# Display.net
KiCad netlist of a schematic drawn in EAGLE
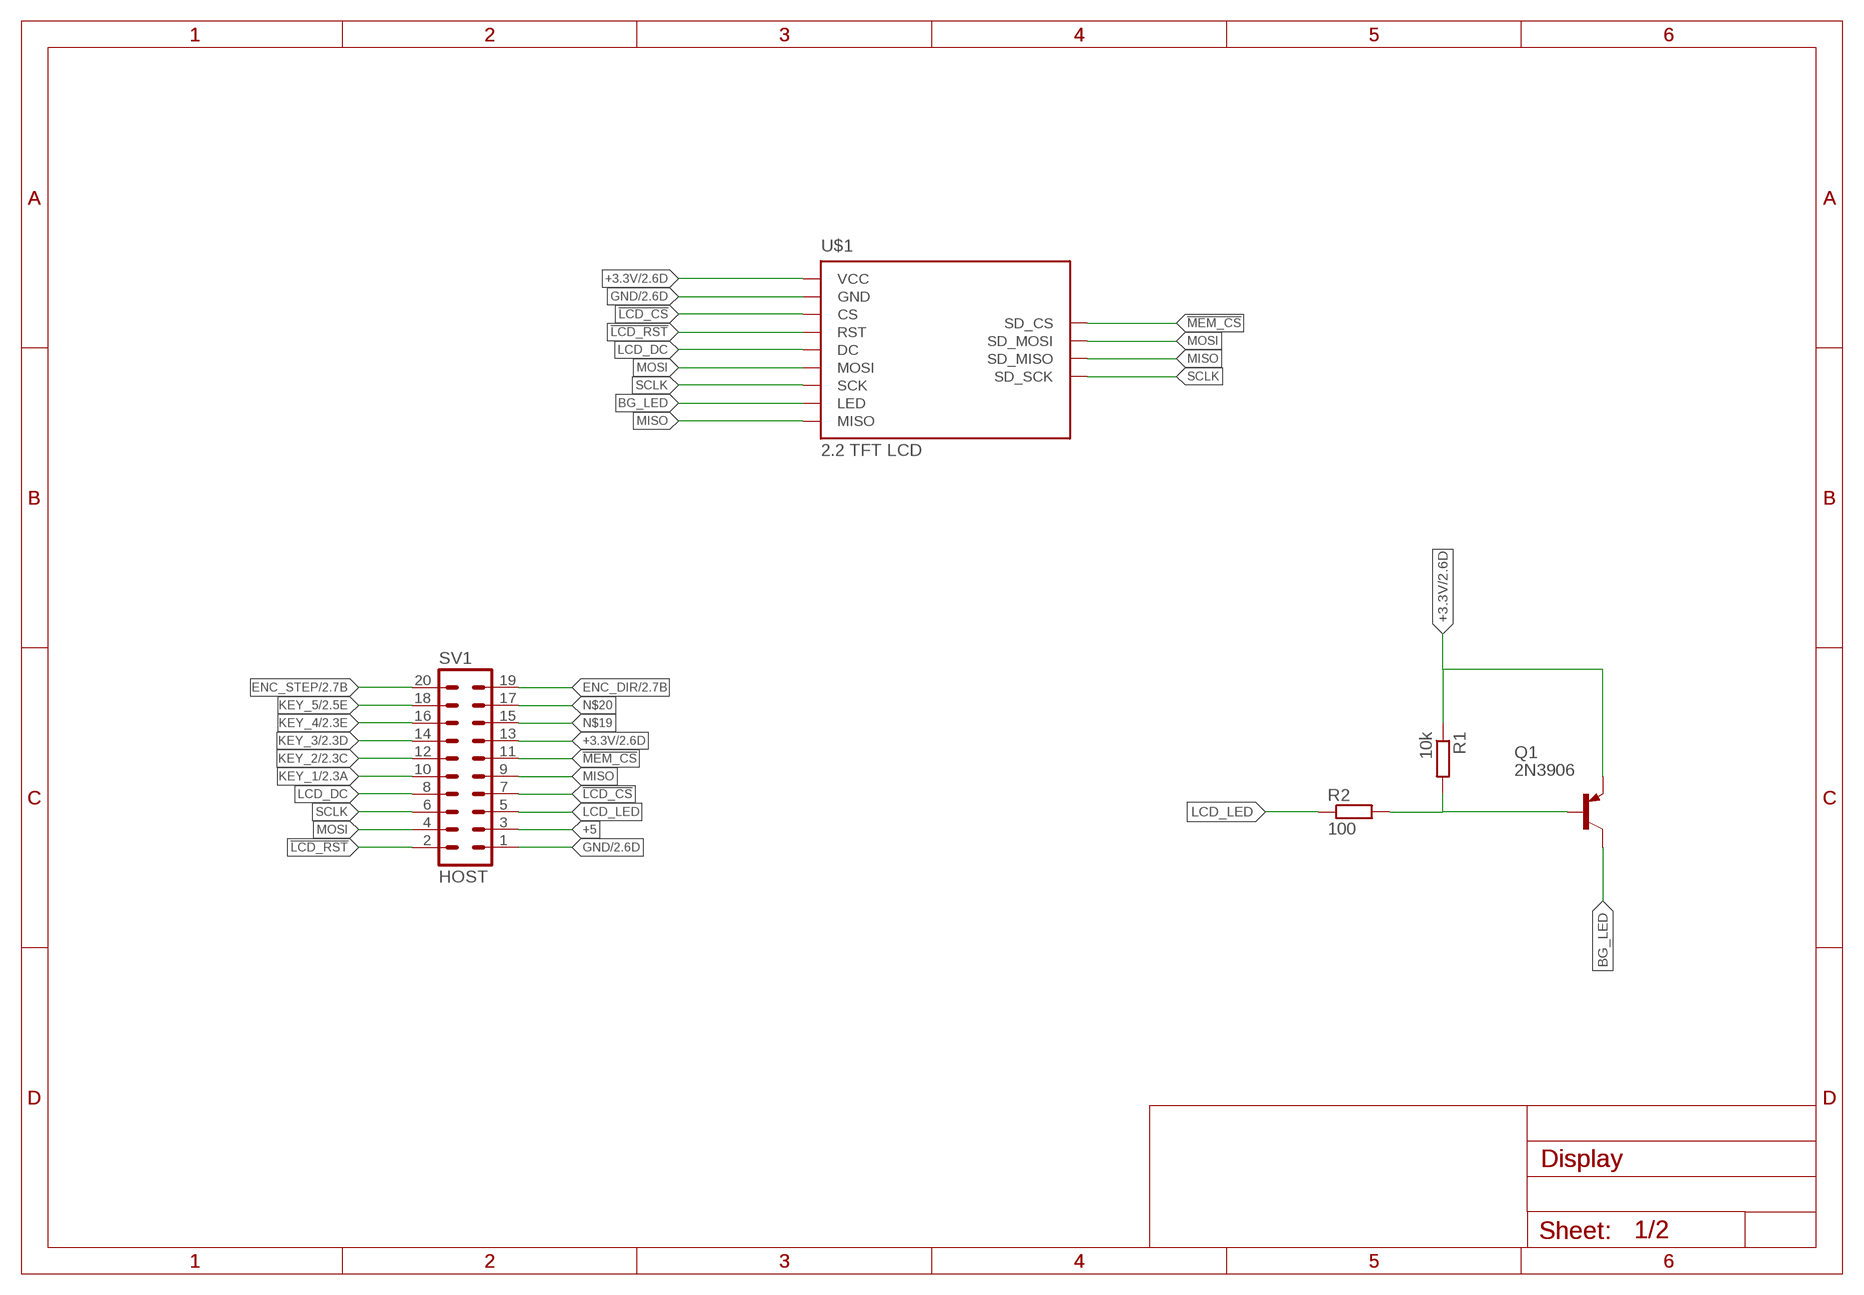
[diagram p0: schematic, sheet 1]
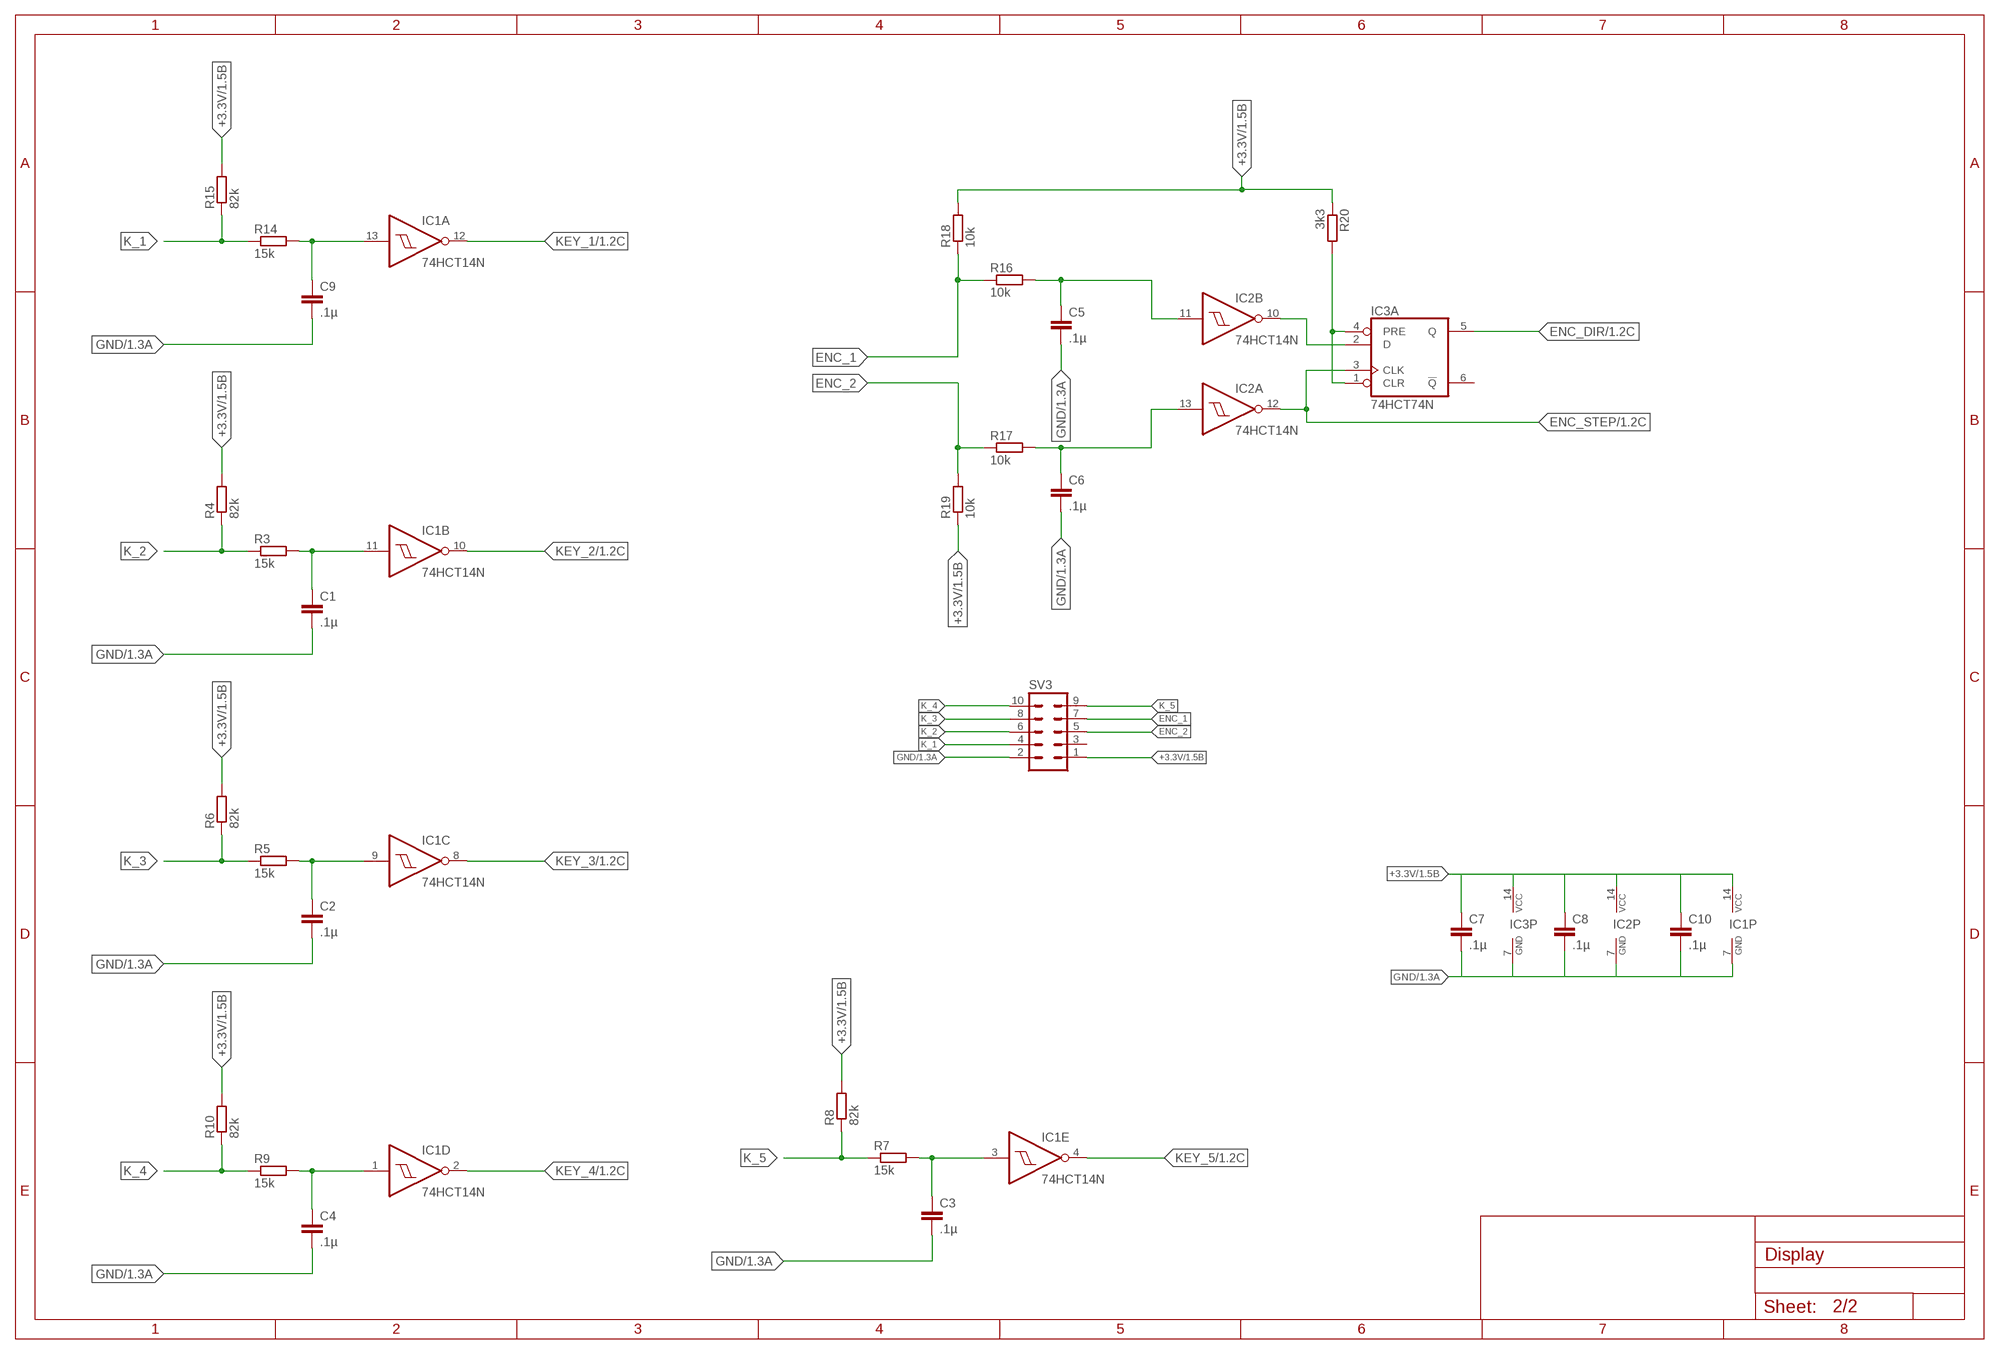
[diagram p1: schematic, sheet 2]

(export (version "E")
  (design (tool "Eeschema 10.0.6"))
  (components
    (comp (ref "Q1")
      (value "2N3906")
      (footprint "eagle-import:TO92")
      (libsource (lib "eagle-import") (part "2N3906"))
    )
    (comp (ref "R1")
      (value "10k")
      (footprint "eagle-import:0204_7")
      (libsource (lib "eagle-import") (part "R-EU_0204/7"))
    )
    (comp (ref "R2")
      (value "100")
      (footprint "eagle-import:0204_7")
      (libsource (lib "eagle-import") (part "R-EU_0204/7"))
    )
    (comp (ref "SV1")
      (value "HOST")
      (footprint "eagle-import:ML20L")
      (libsource (lib "eagle-import") (part "ML20L"))
    )
    (comp (ref "U$1")
      (value "2.2_TFT_LCD")
      (footprint "eagle-import:2.2_TFT_LCD")
      (libsource (lib "eagle-import") (part "2.2_TFT_LCD"))
    )
    (comp (ref "C1")
      (value ".1µ")
      (footprint "eagle-import:C025-024X044")
      (libsource (lib "eagle-import") (part "C-EU025-024X044"))
    )
    (comp (ref "C2")
      (value ".1µ")
      (footprint "eagle-import:C025-024X044")
      (libsource (lib "eagle-import") (part "C-EU025-024X044"))
    )
    (comp (ref "C3")
      (value ".1µ")
      (footprint "eagle-import:C025-024X044")
      (libsource (lib "eagle-import") (part "C-EU025-024X044"))
    )
    (comp (ref "C4")
      (value ".1µ")
      (footprint "eagle-import:C025-024X044")
      (libsource (lib "eagle-import") (part "C-EU025-024X044"))
    )
    (comp (ref "C5")
      (value ".1µ")
      (footprint "eagle-import:C025-024X044")
      (libsource (lib "eagle-import") (part "C-EU025-024X044"))
    )
    (comp (ref "C6")
      (value ".1µ")
      (footprint "eagle-import:C025-024X044")
      (libsource (lib "eagle-import") (part "C-EU025-024X044"))
    )
    (comp (ref "C7")
      (value ".1µ")
      (footprint "eagle-import:C025-024X044")
      (libsource (lib "eagle-import") (part "C-EU025-024X044"))
    )
    (comp (ref "C8")
      (value ".1µ")
      (footprint "eagle-import:C025-024X044")
      (libsource (lib "eagle-import") (part "C-EU025-024X044"))
    )
    (comp (ref "C9")
      (value ".1µ")
      (footprint "eagle-import:C025-024X044")
      (libsource (lib "eagle-import") (part "C-EU025-024X044"))
    )
    (comp (ref "C10")
      (value ".1µ")
      (footprint "eagle-import:C025-024X044")
      (libsource (lib "eagle-import") (part "C-EU025-024X044"))
    )
    (comp (ref "IC1")
      (value "74HCT14N")
      (footprint "eagle-import:DIL14")
      (libsource (lib "eagle-import") (part "7414NHCT"))
    )
    (comp (ref "IC2")
      (value "74HCT14N")
      (footprint "eagle-import:DIL14")
      (libsource (lib "eagle-import") (part "7414NHCT"))
    )
    (comp (ref "IC3")
      (value "74HCT74N")
      (footprint "eagle-import:DIL14")
      (libsource (lib "eagle-import") (part "7474NHCT"))
    )
    (comp (ref "R3")
      (value "15k")
      (footprint "eagle-import:0204_7")
      (libsource (lib "eagle-import") (part "R-EU_0204/7"))
    )
    (comp (ref "R4")
      (value "82k")
      (footprint "eagle-import:0204_7")
      (libsource (lib "eagle-import") (part "R-EU_0204/7"))
    )
    (comp (ref "R5")
      (value "15k")
      (footprint "eagle-import:0204_7")
      (libsource (lib "eagle-import") (part "R-EU_0204/7"))
    )
    (comp (ref "R6")
      (value "82k")
      (footprint "eagle-import:0204_7")
      (libsource (lib "eagle-import") (part "R-EU_0204/7"))
    )
    (comp (ref "R7")
      (value "15k")
      (footprint "eagle-import:0204_7")
      (libsource (lib "eagle-import") (part "R-EU_0204/7"))
    )
    (comp (ref "R8")
      (value "82k")
      (footprint "eagle-import:0204_7")
      (libsource (lib "eagle-import") (part "R-EU_0204/7"))
    )
    (comp (ref "R9")
      (value "15k")
      (footprint "eagle-import:0204_7")
      (libsource (lib "eagle-import") (part "R-EU_0204/7"))
    )
    (comp (ref "R10")
      (value "82k")
      (footprint "eagle-import:0204_7")
      (libsource (lib "eagle-import") (part "R-EU_0204/7"))
    )
    (comp (ref "R14")
      (value "15k")
      (footprint "eagle-import:0204_7")
      (libsource (lib "eagle-import") (part "R-EU_0204/7"))
    )
    (comp (ref "R15")
      (value "82k")
      (footprint "eagle-import:0204_7")
      (libsource (lib "eagle-import") (part "R-EU_0204/7"))
    )
    (comp (ref "R16")
      (value "10k")
      (footprint "eagle-import:0204_7")
      (libsource (lib "eagle-import") (part "R-EU_0204/7"))
    )
    (comp (ref "R17")
      (value "10k")
      (footprint "eagle-import:0204_7")
      (libsource (lib "eagle-import") (part "R-EU_0204/7"))
    )
    (comp (ref "R18")
      (value "10k")
      (footprint "eagle-import:0204_7")
      (libsource (lib "eagle-import") (part "R-EU_0204/7"))
    )
    (comp (ref "R19")
      (value "10k")
      (footprint "eagle-import:0204_7")
      (libsource (lib "eagle-import") (part "R-EU_0204/7"))
    )
    (comp (ref "R20")
      (value "3k3")
      (footprint "eagle-import:0204_7")
      (libsource (lib "eagle-import") (part "R-EU_0204/7"))
    )
    (comp (ref "SV3")
      (value "ML10L")
      (footprint "eagle-import:ML10L")
      (libsource (lib "eagle-import") (part "ML10L"))
    )
  )
  (nets
    (net (code "1") (name "+3.3V") (class "Default")
      (node (ref "C10") (pin "1") (pinfunction "1_1") (pintype "passive"))
      (node (ref "C7") (pin "1") (pinfunction "1_1") (pintype "passive"))
      (node (ref "C8") (pin "1") (pinfunction "1_1") (pintype "passive"))
      (node (ref "IC1") (pin "14") (pinfunction "VCC_14") (pintype "power_in"))
      (node (ref "IC2") (pin "14") (pinfunction "VCC_14") (pintype "power_in"))
      (node (ref "IC3") (pin "14") (pinfunction "VCC_14") (pintype "power_in"))
      (node (ref "Q1") (pin "3") (pinfunction "E_3") (pintype "passive"))
      (node (ref "R1") (pin "1") (pinfunction "1_1") (pintype "passive"))
      (node (ref "R10") (pin "2") (pinfunction "2_2") (pintype "passive"))
      (node (ref "R15") (pin "2") (pinfunction "2_2") (pintype "passive"))
      (node (ref "R18") (pin "2") (pinfunction "2_2") (pintype "passive"))
      (node (ref "R19") (pin "1") (pinfunction "1_1") (pintype "passive"))
      (node (ref "R20") (pin "1") (pinfunction "1_1") (pintype "passive"))
      (node (ref "R4") (pin "2") (pinfunction "2_2") (pintype "passive"))
      (node (ref "R6") (pin "2") (pinfunction "2_2") (pintype "passive"))
      (node (ref "R8") (pin "2") (pinfunction "2_2") (pintype "passive"))
      (node (ref "SV1") (pin "13") (pinfunction "13_13") (pintype "passive"))
      (node (ref "SV3") (pin "1") (pinfunction "1_1") (pintype "passive"))
      (node (ref "U$1") (pin "VCC") (pinfunction "VCC_VCC") (pintype "power_in"))
    )
    (net (code "2") (name "+5") (class "Default")
      (node (ref "SV1") (pin "3") (pinfunction "3_3") (pintype "passive"))
    )
    (net (code "3") (name "BG_LED") (class "Default")
      (node (ref "Q1") (pin "1") (pinfunction "C_1") (pintype "passive"))
      (node (ref "U$1") (pin "LED") (pinfunction "LED_LED") (pintype "bidirectional"))
    )
    (net (code "4") (name "ENC_1") (class "Default")
      (node (ref "R16") (pin "1") (pinfunction "1_1") (pintype "passive"))
      (node (ref "R18") (pin "1") (pinfunction "1_1") (pintype "passive"))
      (node (ref "SV3") (pin "7") (pinfunction "7_7") (pintype "passive"))
    )
    (net (code "5") (name "ENC_2") (class "Default")
      (node (ref "R17") (pin "1") (pinfunction "1_1") (pintype "passive"))
      (node (ref "R19") (pin "2") (pinfunction "2_2") (pintype "passive"))
      (node (ref "SV3") (pin "5") (pinfunction "5_5") (pintype "passive"))
    )
    (net (code "6") (name "ENC_DIR") (class "Default")
      (node (ref "IC3") (pin "5") (pinfunction "Q_5") (pintype "output"))
      (node (ref "SV1") (pin "19") (pinfunction "19_19") (pintype "passive"))
    )
    (net (code "7") (name "ENC_STEP") (class "Default")
      (node (ref "IC2") (pin "12") (pinfunction "O_12") (pintype "output"))
      (node (ref "IC3") (pin "3") (pinfunction "CLK_3") (pintype "input"))
      (node (ref "SV1") (pin "20") (pinfunction "20_20") (pintype "passive"))
    )
    (net (code "8") (name "GND") (class "Default")
      (node (ref "C1") (pin "2") (pinfunction "2_2") (pintype "passive"))
      (node (ref "C10") (pin "2") (pinfunction "2_2") (pintype "passive"))
      (node (ref "C2") (pin "2") (pinfunction "2_2") (pintype "passive"))
      (node (ref "C3") (pin "2") (pinfunction "2_2") (pintype "passive"))
      (node (ref "C4") (pin "2") (pinfunction "2_2") (pintype "passive"))
      (node (ref "C5") (pin "2") (pinfunction "2_2") (pintype "passive"))
      (node (ref "C6") (pin "2") (pinfunction "2_2") (pintype "passive"))
      (node (ref "C7") (pin "2") (pinfunction "2_2") (pintype "passive"))
      (node (ref "C8") (pin "2") (pinfunction "2_2") (pintype "passive"))
      (node (ref "C9") (pin "2") (pinfunction "2_2") (pintype "passive"))
      (node (ref "IC1") (pin "7") (pinfunction "GND_7") (pintype "power_in"))
      (node (ref "IC2") (pin "7") (pinfunction "GND_7") (pintype "power_in"))
      (node (ref "IC3") (pin "7") (pinfunction "GND_7") (pintype "power_in"))
      (node (ref "SV1") (pin "1") (pinfunction "1_1") (pintype "passive"))
      (node (ref "SV3") (pin "2") (pinfunction "2_2") (pintype "passive"))
      (node (ref "U$1") (pin "GND") (pinfunction "GND_GND") (pintype "power_in"))
    )
    (net (code "9") (name "KEY_1") (class "Default")
      (node (ref "IC1") (pin "12") (pinfunction "O_12") (pintype "output"))
      (node (ref "SV1") (pin "10") (pinfunction "10_10") (pintype "passive"))
    )
    (net (code "10") (name "KEY_2") (class "Default")
      (node (ref "IC1") (pin "10") (pinfunction "O_10") (pintype "output"))
      (node (ref "SV1") (pin "12") (pinfunction "12_12") (pintype "passive"))
    )
    (net (code "11") (name "KEY_3") (class "Default")
      (node (ref "IC1") (pin "8") (pinfunction "O_8") (pintype "output"))
      (node (ref "SV1") (pin "14") (pinfunction "14_14") (pintype "passive"))
    )
    (net (code "12") (name "KEY_4") (class "Default")
      (node (ref "IC1") (pin "2") (pinfunction "O_2") (pintype "output"))
      (node (ref "SV1") (pin "16") (pinfunction "16_16") (pintype "passive"))
    )
    (net (code "13") (name "KEY_5") (class "Default")
      (node (ref "IC1") (pin "4") (pinfunction "O_4") (pintype "output"))
      (node (ref "SV1") (pin "18") (pinfunction "18_18") (pintype "passive"))
    )
    (net (code "14") (name "K_1") (class "Default")
      (node (ref "R14") (pin "1") (pinfunction "1_1") (pintype "passive"))
      (node (ref "R15") (pin "1") (pinfunction "1_1") (pintype "passive"))
      (node (ref "SV3") (pin "4") (pinfunction "4_4") (pintype "passive"))
    )
    (net (code "15") (name "K_2") (class "Default")
      (node (ref "R3") (pin "1") (pinfunction "1_1") (pintype "passive"))
      (node (ref "R4") (pin "1") (pinfunction "1_1") (pintype "passive"))
      (node (ref "SV3") (pin "6") (pinfunction "6_6") (pintype "passive"))
    )
    (net (code "16") (name "K_3") (class "Default")
      (node (ref "R5") (pin "1") (pinfunction "1_1") (pintype "passive"))
      (node (ref "R6") (pin "1") (pinfunction "1_1") (pintype "passive"))
      (node (ref "SV3") (pin "8") (pinfunction "8_8") (pintype "passive"))
    )
    (net (code "17") (name "K_4") (class "Default")
      (node (ref "R10") (pin "1") (pinfunction "1_1") (pintype "passive"))
      (node (ref "R9") (pin "1") (pinfunction "1_1") (pintype "passive"))
      (node (ref "SV3") (pin "10") (pinfunction "10_10") (pintype "passive"))
    )
    (net (code "18") (name "K_5") (class "Default")
      (node (ref "R7") (pin "1") (pinfunction "1_1") (pintype "passive"))
      (node (ref "R8") (pin "1") (pinfunction "1_1") (pintype "passive"))
      (node (ref "SV3") (pin "9") (pinfunction "9_9") (pintype "passive"))
    )
    (net (code "19") (name "LCD_DC") (class "Default")
      (node (ref "SV1") (pin "8") (pinfunction "8_8") (pintype "passive"))
      (node (ref "U$1") (pin "DC") (pinfunction "DC_DC") (pintype "bidirectional"))
    )
    (net (code "20") (name "LCD_LED") (class "Default")
      (node (ref "R2") (pin "1") (pinfunction "1_1") (pintype "passive"))
      (node (ref "SV1") (pin "5") (pinfunction "5_5") (pintype "passive"))
    )
    (net (code "21") (name "MISO") (class "Default")
      (node (ref "SV1") (pin "9") (pinfunction "9_9") (pintype "passive"))
      (node (ref "U$1") (pin "MISO") (pinfunction "MISO_MISO") (pintype "bidirectional"))
      (node (ref "U$1") (pin "SD_MISO") (pinfunction "SD_MISO_SD_MISO") (pintype "bidirectional"))
    )
    (net (code "22") (name "MOSI") (class "Default")
      (node (ref "SV1") (pin "4") (pinfunction "4_4") (pintype "passive"))
      (node (ref "U$1") (pin "MOSI") (pinfunction "MOSI_MOSI") (pintype "bidirectional"))
      (node (ref "U$1") (pin "SD_MOSI") (pinfunction "SD_MOSI_SD_MOSI") (pintype "bidirectional"))
    )
    (net (code "23") (name "N$19") (class "Default")
      (node (ref "SV1") (pin "15") (pinfunction "15_15") (pintype "passive"))
    )
    (net (code "24") (name "N$20") (class "Default")
      (node (ref "SV1") (pin "17") (pinfunction "17_17") (pintype "passive"))
    )
    (net (code "25") (name "Net-(IC1A-I)") (class "Default")
      (node (ref "C9") (pin "1") (pinfunction "1_1") (pintype "passive"))
      (node (ref "IC1") (pin "13") (pinfunction "I_13") (pintype "input"))
      (node (ref "R14") (pin "2") (pinfunction "2_2") (pintype "passive"))
    )
    (net (code "26") (name "Net-(IC1B-I)") (class "Default")
      (node (ref "C1") (pin "1") (pinfunction "1_1") (pintype "passive"))
      (node (ref "IC1") (pin "11") (pinfunction "I_11") (pintype "input"))
      (node (ref "R3") (pin "2") (pinfunction "2_2") (pintype "passive"))
    )
    (net (code "27") (name "Net-(IC1C-I)") (class "Default")
      (node (ref "C2") (pin "1") (pinfunction "1_1") (pintype "passive"))
      (node (ref "IC1") (pin "9") (pinfunction "I_9") (pintype "input"))
      (node (ref "R5") (pin "2") (pinfunction "2_2") (pintype "passive"))
    )
    (net (code "28") (name "Net-(IC1D-I)") (class "Default")
      (node (ref "C4") (pin "1") (pinfunction "1_1") (pintype "passive"))
      (node (ref "IC1") (pin "1") (pinfunction "I_1") (pintype "input"))
      (node (ref "R9") (pin "2") (pinfunction "2_2") (pintype "passive"))
    )
    (net (code "29") (name "Net-(IC1E-I)") (class "Default")
      (node (ref "C3") (pin "1") (pinfunction "1_1") (pintype "passive"))
      (node (ref "IC1") (pin "3") (pinfunction "I_3") (pintype "input"))
      (node (ref "R7") (pin "2") (pinfunction "2_2") (pintype "passive"))
    )
    (net (code "30") (name "Net-(IC2A-I)") (class "Default")
      (node (ref "C6") (pin "1") (pinfunction "1_1") (pintype "passive"))
      (node (ref "IC2") (pin "13") (pinfunction "I_13") (pintype "input"))
      (node (ref "R17") (pin "2") (pinfunction "2_2") (pintype "passive"))
    )
    (net (code "31") (name "Net-(IC2B-I)") (class "Default")
      (node (ref "C5") (pin "1") (pinfunction "1_1") (pintype "passive"))
      (node (ref "IC2") (pin "11") (pinfunction "I_11") (pintype "input"))
      (node (ref "R16") (pin "2") (pinfunction "2_2") (pintype "passive"))
    )
    (net (code "32") (name "Net-(IC2B-O)") (class "Default")
      (node (ref "IC2") (pin "10") (pinfunction "O_10") (pintype "output"))
      (node (ref "IC3") (pin "2") (pinfunction "D_2") (pintype "input"))
    )
    (net (code "33") (name "Net-(IC3A-CLR)") (class "Default")
      (node (ref "IC3") (pin "1") (pinfunction "CLR_1") (pintype "input"))
      (node (ref "IC3") (pin "4") (pinfunction "PRE_4") (pintype "input"))
      (node (ref "R20") (pin "2") (pinfunction "2_2") (pintype "passive"))
    )
    (net (code "34") (name "Net-(Q1-B)") (class "Default")
      (node (ref "Q1") (pin "2") (pinfunction "B_2") (pintype "passive"))
      (node (ref "R1") (pin "2") (pinfunction "2_2") (pintype "passive"))
      (node (ref "R2") (pin "2") (pinfunction "2_2") (pintype "passive"))
    )
    (net (code "35") (name "SCLK") (class "Default")
      (node (ref "SV1") (pin "6") (pinfunction "6_6") (pintype "passive"))
      (node (ref "U$1") (pin "SCK") (pinfunction "SCK_SCK") (pintype "bidirectional"))
      (node (ref "U$1") (pin "SD_SCK") (pinfunction "SD_SCK_SD_SCK") (pintype "bidirectional"))
    )
    (net (code "36") (name "unconnected-(IC3A-~{Q}-Pad6)") (class "Default")
      (node (ref "IC3") (pin "6") (pinfunction "~{Q}_6") (pintype "output"))
    )
    (net (code "37") (name "unconnected-(SV3-Pad3)") (class "Default")
      (node (ref "SV3") (pin "3") (pinfunction "3_3") (pintype "passive"))
    )
    (net (code "38") (name "~{LCD_CS}") (class "Default")
      (node (ref "SV1") (pin "7") (pinfunction "7_7") (pintype "passive"))
      (node (ref "U$1") (pin "CS") (pinfunction "CS_CS") (pintype "bidirectional"))
    )
    (net (code "39") (name "~{LCD_RST}") (class "Default")
      (node (ref "SV1") (pin "2") (pinfunction "2_2") (pintype "passive"))
      (node (ref "U$1") (pin "RST") (pinfunction "RST_RST") (pintype "bidirectional"))
    )
    (net (code "40") (name "~{MEM_CS}") (class "Default")
      (node (ref "SV1") (pin "11") (pinfunction "11_11") (pintype "passive"))
      (node (ref "U$1") (pin "SD_CS") (pinfunction "SD_CS_SD_CS") (pintype "bidirectional"))
    )
  )
)
